# 3-PM25-STM32F103C8-170426.net
KiCad netlist of a schematic drawn in Altium Designer
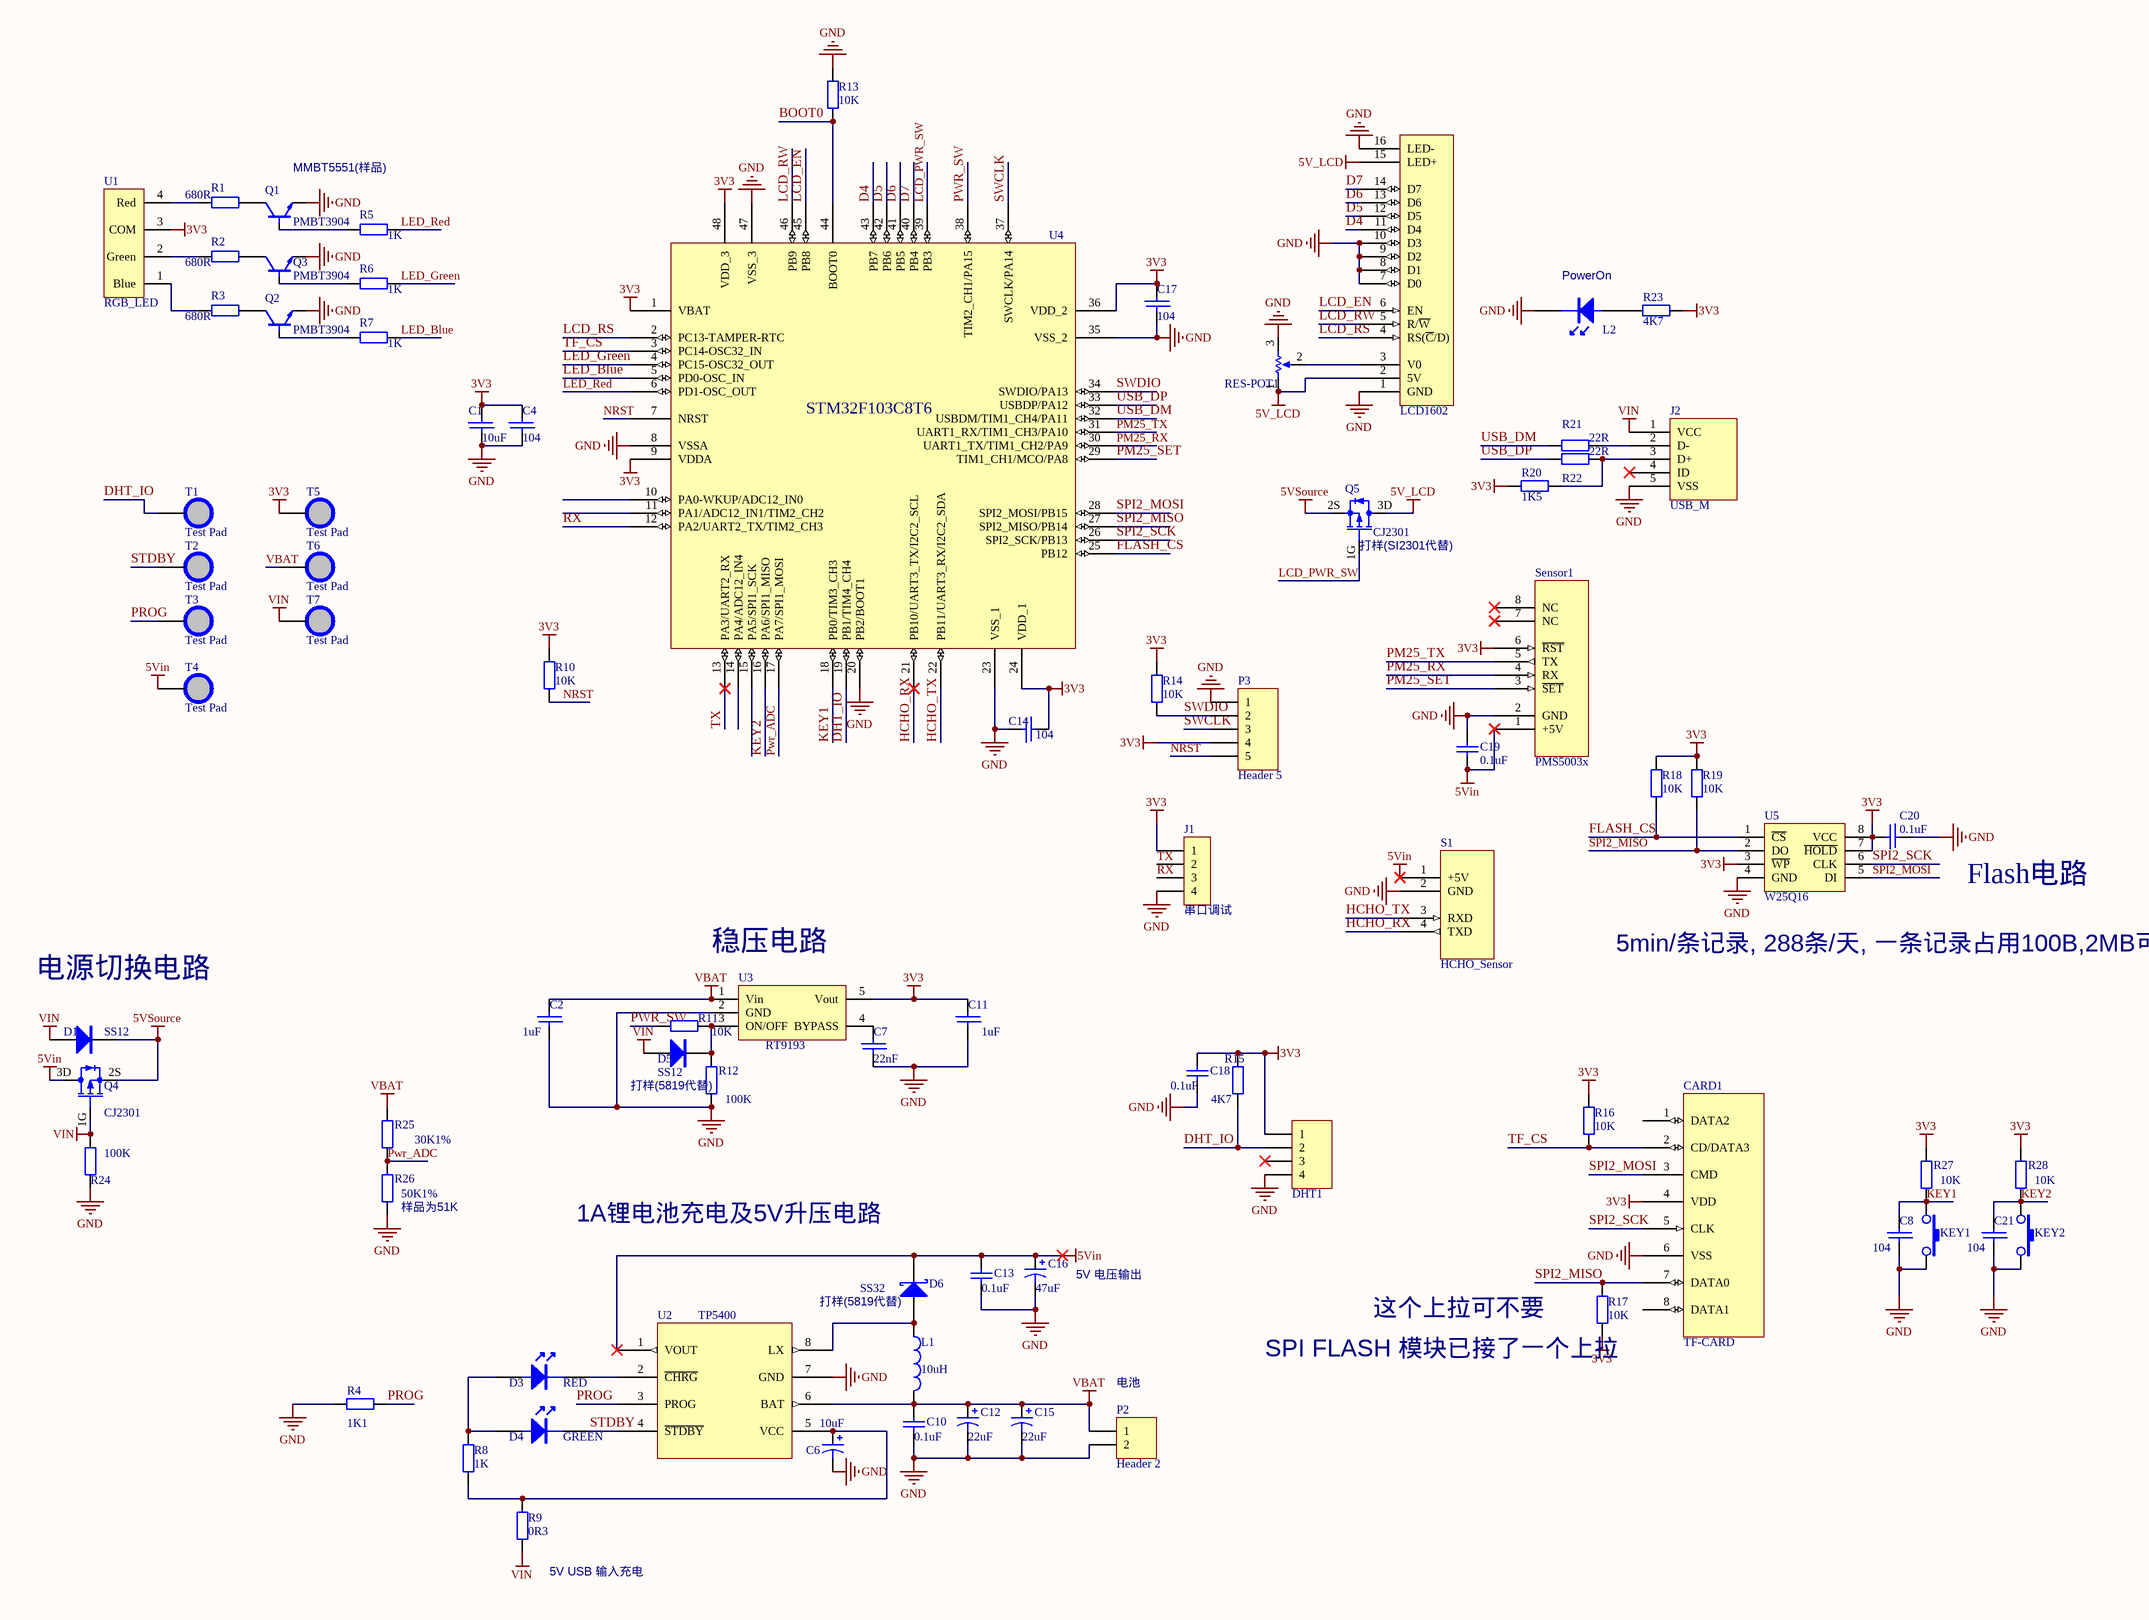
[diagram p0: 3-PM25-STM32F103C8-170426.SchDoc]

(export (version "E")
  (design (tool "Eeschema 10.0.6"))
  (components
    (comp (ref "C1")
      (value "10uF")
      (footprint "LC0805_Std")
      (fields (field (name "Comment") "10uF (106) ±10% 25V,0805"))
      (libsource (lib "元件总库") (part "普通电容"))
    )
    (comp (ref "C2")
      (value "1uF (105) ±10% 50V ,0603")
      (footprint "LC0603_Std")
      (fields (field (name "ALTIUM_UNNAMED_1") "1uF"))
      (libsource (lib "元件总库") (part "普通电容"))
    )
    (comp (ref "C4")
      (value "104")
      (footprint "LC0603_Std")
      (fields (field (name "Comment") "100nF(104) ±10% 50V,0603"))
      (libsource (lib "元件总库") (part "普通电容"))
    )
    (comp (ref "C6")
      (value "10uF")
      (footprint "LC0805_Std")
      (fields (field (name "Comment") "10uF (106) ±10% 25V,0805") (field (name "PUBLISHER") "Altium Limited"))
      (libsource (lib "Miscellaneous Devices") (part "Cap Pol1"))
    )
    (comp (ref "C7")
      (value "22nF (223) ±10% 50V,0603")
      (footprint "LC0603_Std")
      (fields (field (name "ALTIUM_UNNAMED_1") "22nF"))
      (libsource (lib "元件总库") (part "普通电容"))
    )
    (comp (ref "C8")
      (value "104")
      (footprint "LC0603_Std")
      (fields (field (name "Comment") "100nF (104) ±10% 50V,0603"))
      (libsource (lib "元件总库") (part "普通电容"))
    )
    (comp (ref "C10")
      (value "0.1uF")
      (footprint "LC0603_Std")
      (fields (field (name "Comment") "100nF(104) ±10% 50V,0603") (field (name "PUBLISHER") "Altium Limited"))
      (libsource (lib "Miscellaneous Devices") (part "Cap"))
    )
    (comp (ref "C11")
      (value "1uF (105) ±10% 50V ,0603")
      (footprint "LC0603_Std")
      (fields (field (name "ALTIUM_UNNAMED_1") "1uF"))
      (libsource (lib "元件总库") (part "普通电容"))
    )
    (comp (ref "C12")
      (value "22uF")
      (footprint "LC0805_Std")
      (fields (field (name "Comment") "22uF (226) ±20% 25V,0805") (field (name "PUBLISHER") "Altium Limited"))
      (libsource (lib "Miscellaneous Devices") (part "Cap Pol1"))
    )
    (comp (ref "C13")
      (value "0.1uF")
      (footprint "LC0603_Std")
      (fields (field (name "Comment") "100nF(104) ±10% 50V,0603") (field (name "PUBLISHER") "Altium Limited"))
      (libsource (lib "Miscellaneous Devices") (part "Cap"))
    )
    (comp (ref "C14")
      (value "104")
      (footprint "LC0603_Std")
      (fields (field (name "Comment") "100nF(104) ±10% 50V,0603"))
      (libsource (lib "元件总库") (part "普通电容"))
    )
    (comp (ref "C15")
      (value "22uF")
      (footprint "LC0805_Std")
      (fields (field (name "Comment") "22uF (226) ±20% 25V,0805") (field (name "PUBLISHER") "Altium Limited"))
      (libsource (lib "Miscellaneous Devices") (part "Cap Pol1"))
    )
    (comp (ref "C16")
      (value "47uF")
      (footprint "Cap-4x7")
      (fields (field (name "Comment") "47uF 16V,4*7,电解电容") (field (name "PUBLISHER") "Altium Limited"))
      (libsource (lib "Miscellaneous Devices") (part "Cap Pol1"))
    )
    (comp (ref "C17")
      (value "104")
      (footprint "LC0603_Std")
      (fields (field (name "Comment") "100nF(104) ±10% 50V,0603"))
      (libsource (lib "元件总库") (part "普通电容"))
    )
    (comp (ref "C18")
      (value "0.1uF")
      (footprint "LC0603_Std")
      (description "Capacitor")
      (fields (field (name "Comment") "100nF(104) ±10% 50V,0603") (field (name "PUBLISHER") "Altium Limited"))
      (libsource (lib "Miscellaneous Devices") (part "Cap"))
    )
    (comp (ref "C19")
      (value "0.1uF")
      (footprint "LC0603_Std")
      (description "Capacitor")
      (fields (field (name "Comment") "100nF(104) ±10% 50V,0603") (field (name "PUBLISHER") "Altium Limited"))
      (libsource (lib "Miscellaneous Devices") (part "Cap"))
    )
    (comp (ref "C20")
      (value "100nF(104) ±10% 50V,0603")
      (footprint "LC0603_Std")
      (fields (field (name "ALTIUM_UNNAMED_1") "0.1uF"))
      (libsource (lib "元件总库") (part "普通电容"))
    )
    (comp (ref "C21")
      (value "104")
      (footprint "LC0603_Std")
      (fields (field (name "Comment") "100nF (104) ±10% 50V,0603"))
      (libsource (lib "元件总库") (part "普通电容"))
    )
    (comp (ref "CARD1")
      (value "TF-CARD")
      (footprint "TF-CARD")
      (libsource (lib "My_SchLib_2014_04_01") (part "TF-CARD"))
    )
    (comp (ref "D1")
      (value "5819,SS12")
      (footprint "SOD-123-5819")
      (fields (field (name "ALTIUM_UNNAMED_1") "SS12"))
      (libsource (lib "元件总库") (part "二极管"))
    )
    (comp (ref "D3")
      (value "RED")
      (footprint "LC0603_Std")
      (fields (field (name "Comment") "红灯,发光二极, C2286,0603"))
      (libsource (lib "Miscellaneous Devices") (part "LED"))
    )
    (comp (ref "D4")
      (value "GREEN")
      (footprint "LC0603_Std")
      (fields (field (name "Comment") "绿灯,发光二极, C72043, 0603"))
      (libsource (lib "Miscellaneous Devices") (part "LED"))
    )
    (comp (ref "D5")
      (value "5819,SS12")
      (footprint "SOD-123-5819")
      (fields (field (name "ALTIUM_UNNAMED_1") "SS12"))
      (libsource (lib "元件总库") (part "二极管"))
    )
    (comp (ref "D6")
      (value "B5819W SL,SOD123,SS32,20V,3A,VF=0.55V@3A,DO-214AC")
      (footprint "SOD-123-5819")
      (fields (field (name "NAME") "SS32") (field (name "PUBLISHER") "Altium Limited"))
      (libsource (lib "Miscellaneous Devices") (part "D Schottky"))
    )
    (comp (ref "DHT1")
      (value "Header 4")
      (footprint "DHT11")
      (description "接插件")
      (fields (field (name "PUBLISHER") "Altium Limited"))
      (libsource (lib "fszhang") (part "Header 4"))
    )
    (comp (ref "J1") (value "串口调试") (footprint "HDR1X4") (libsource (lib "排针") (part "CON4")))
    (comp (ref "J2")
      (value "USB_M")
      (footprint "micro-USB-B")
      (description "MicroUSB接口")
      (libsource (lib "fszhang") (part "USB_M"))
    )
    (comp (ref "KEY1") (value "轻触开关") (footprint "轻触开关-6x6x6") (libsource (lib "元件总库") (part "轻触开关")))
    (comp (ref "KEY2") (value "轻触开关") (footprint "轻触开关-6x6x6") (libsource (lib "元件总库") (part "轻触开关")))
    (comp (ref "L1")
      (value "10uH")
      (footprint "LC0603_Std")
      (fields (field (name "Comment") "10uH ±10%,0603") (field (name "PUBLISHER") "Altium Limited"))
      (libsource (lib "Miscellaneous Devices") (part "Inductor"))
    )
    (comp (ref "L2")
      (value "单色蓝灯, 发光二极管,0603")
      (footprint "LC0603_Std")
      (libsource (lib "Miscellaneous Devices") (part "LED"))
    )
    (comp (ref "LCD1")
      (value "LCD1602")
      (footprint "LCD1602_KS0066")
      (libsource (lib "My_SchLib_2014_04_01") (part "LCD1602_KS0066"))
    )
    (comp (ref "P2")
      (value "Header 2")
      (footprint "XH-2A-2P")
      (description "Header, 2-Pin")
      (fields (field (name "PUBLISHER") "Altium Limited"))
      (libsource (lib "Miscellaneous Connectors") (part "Header 2"))
    )
    (comp (ref "P3")
      (value "Header 5")
      (footprint "HDR1X5")
      (description "Header, 5-Pin")
      (fields (field (name "PUBLISHER") "Altium Limited"))
      (libsource (lib "Miscellaneous Connectors") (part "Header 5"))
    )
    (comp (ref "Q1") (value "PMBT3904") (footprint "SOT23-NPN") (libsource (lib "元件总库") (part "NPN")))
    (comp (ref "Q2") (value "PMBT3904") (footprint "SOT23-NPN") (libsource (lib "元件总库") (part "NPN")))
    (comp (ref "Q3") (value "PMBT3904") (footprint "SOT23-NPN") (libsource (lib "元件总库") (part "NPN")))
    (comp (ref "Q4")
      (value "CJ2301")
      (footprint "SOT-23_SI2301")
      (libsource (lib "My_SchLib_2014_04_01") (part "PMOS"))
    )
    (comp (ref "Q5") (value "CJ2301") (footprint "SOT-23_SI2301") (libsource (lib "") (part "PMOS_1")))
    (comp (ref "R1")
      (value "680R")
      (footprint "LC0603_Std")
      (fields (field (name "Comment") "680Ω (6800) ±1%"))
      (libsource (lib "元件总库") (part "电阻"))
    )
    (comp (ref "R2")
      (value "680R")
      (footprint "LC0603_Std")
      (fields (field (name "Comment") "680Ω (6800) ±1%"))
      (libsource (lib "元件总库") (part "电阻"))
    )
    (comp (ref "R3")
      (value "680R")
      (footprint "LC0603_Std")
      (fields (field (name "Comment") "680Ω (6800) ±1%"))
      (libsource (lib "元件总库") (part "电阻"))
    )
    (comp (ref "R4")
      (value "1K1")
      (footprint "LC0603_Std")
      (description "Resistor")
      (fields (field (name "Comment") "1.1KΩ (1101) ±1%,0603") (field (name "PUBLISHER") "Altium Limited"))
      (libsource (lib "") (part "Res2_3"))
    )
    (comp (ref "R5")
      (value "1K")
      (footprint "LC0603_Std")
      (fields (field (name "Comment") "1KΩ (1001) ±1%,0603"))
      (libsource (lib "元件总库") (part "电阻"))
    )
    (comp (ref "R6")
      (value "1K")
      (footprint "LC0603_Std")
      (fields (field (name "Comment") "1KΩ (1001) ±1%,0603"))
      (libsource (lib "元件总库") (part "电阻"))
    )
    (comp (ref "R7")
      (value "1K")
      (footprint "LC0603_Std")
      (fields (field (name "Comment") "1KΩ (1001) ±1%,0603"))
      (libsource (lib "元件总库") (part "电阻"))
    )
    (comp (ref "R8")
      (value "1K")
      (footprint "LC0603_Std")
      (description "Resistor")
      (fields (field (name "Comment") "1KΩ (1001) ±1%,0603") (field (name "PUBLISHER") "Altium Limited"))
      (libsource (lib "") (part "Res2_2"))
    )
    (comp (ref "R9")
      (value "0R3")
      (footprint "LC0805_Std")
      (description "Resistor")
      (fields (field (name "Comment") "0.3Ω (R300) ±1%,0805") (field (name "PUBLISHER") "Altium Limited"))
      (libsource (lib "Miscellaneous Devices") (part "Res2"))
    )
    (comp (ref "R10")
      (value "10K")
      (footprint "LC0603_Std")
      (description "Risistor")
      (fields (field (name "Comment") "10KΩ (1002) ±1%,0603"))
      (libsource (lib "") (part "Res-C0805_1"))
    )
    (comp (ref "R11")
      (value "10KΩ (1002) ±1%,0603")
      (footprint "LC0603_Std")
      (fields (field (name "ALTIUM_UNNAMED_1") "10K"))
      (libsource (lib "元件总库") (part "电阻"))
    )
    (comp (ref "R12")
      (value "100KΩ (1003) ±1%,0603")
      (footprint "LC0603_Std")
      (fields (field (name "ALTIUM_UNNAMED_1") "100K"))
      (libsource (lib "元件总库") (part "电阻"))
    )
    (comp (ref "R13")
      (value "10K")
      (footprint "LC0603_Std")
      (description "Risistor")
      (fields (field (name "Comment") "10KΩ (1002) ±1%,0603"))
      (libsource (lib "") (part "Res-C0805_1"))
    )
    (comp (ref "R14")
      (value "10K")
      (footprint "LC0603_Std")
      (description "Risistor")
      (fields (field (name "Comment") "10KΩ (1002) ±1%,0603"))
      (libsource (lib "") (part "Res-C0805_2"))
    )
    (comp (ref "R15")
      (value "4K7")
      (footprint "LC0603_Std")
      (description "Resistor")
      (fields (field (name "Comment") "4.7KΩ (4701) ±1%,0603") (field (name "PUBLISHER") "Altium Limited"))
      (libsource (lib "Miscellaneous Devices") (part "Res2"))
    )
    (comp (ref "R16")
      (value "10K")
      (footprint "LC0603_Std")
      (description "Risistor")
      (fields (field (name "Comment") "10KΩ (1002) ±1%,0603"))
      (libsource (lib "") (part "Res-C0805_2"))
    )
    (comp (ref "R17")
      (value "10K")
      (footprint "LC0603_Std")
      (description "Risistor")
      (fields (field (name "Comment") "10KΩ (1002) ±1%,0603"))
      (libsource (lib "") (part "Res-C0805_2"))
    )
    (comp (ref "R18")
      (value "10K")
      (footprint "LC0603_Std")
      (description "Risistor")
      (fields (field (name "Comment") "10KΩ (1002) ±1%,0603"))
      (libsource (lib "") (part "Res-C0805_2"))
    )
    (comp (ref "R19")
      (value "10K")
      (footprint "LC0603_Std")
      (description "Risistor")
      (fields (field (name "Comment") "10KΩ (1002) ±1%,0603"))
      (libsource (lib "") (part "Res-C0805_2"))
    )
    (comp (ref "R20")
      (value "1K5")
      (footprint "LC0603_Std")
      (description "Risistor")
      (fields (field (name "Comment") "1.5KΩ (1501) ±1%,0603"))
      (libsource (lib "My_Integrated_Library") (part "Res-C0805"))
    )
    (comp (ref "R21")
      (value "22R")
      (footprint "LC0603_Std")
      (description "Risistor")
      (fields (field (name "Comment") "22Ω (22R0) ±1%,0603"))
      (libsource (lib "My_Integrated_Library") (part "Res-C0805"))
    )
    (comp (ref "R22")
      (value "22R")
      (footprint "LC0603_Std")
      (description "Risistor")
      (fields (field (name "Comment") "22Ω (22R0) ±1%,0603"))
      (libsource (lib "My_Integrated_Library") (part "Res-C0805"))
    )
    (comp (ref "R23")
      (value "4K7")
      (footprint "LC0603_Std")
      (description "Resistor")
      (fields (field (name "Comment") "4.7KΩ (4701) ±1%,0603") (field (name "PUBLISHER") "Altium Limited"))
      (libsource (lib "") (part "Res2_1"))
    )
    (comp (ref "R24")
      (value "100KΩ (1003) ±1%,0603")
      (footprint "LC0603_Std")
      (fields (field (name "ALTIUM_UNNAMED_1") "100K"))
      (libsource (lib "元件总库") (part "电阻"))
    )
    (comp (ref "R25")
      (value "30KΩ (3002) ±1% ,0603")
      (footprint "LC0603_Std")
      (fields (field (name "ALTIUM_UNNAMED_1") "30K1%"))
      (libsource (lib "元件总库") (part "电阻"))
    )
    (comp (ref "R26")
      (value "51KΩ (5102) ±1%")
      (footprint "LC0603_Std")
      (fields (field (name "ALTIUM_UNNAMED_1") "50K1%"))
      (libsource (lib "元件总库") (part "电阻"))
    )
    (comp (ref "R27")
      (value "10K")
      (footprint "LC0603_Std")
      (fields (field (name "Comment") "10KΩ (1002) ±1%,0603"))
      (libsource (lib "") (part "电阻_1"))
    )
    (comp (ref "R28")
      (value "10K")
      (footprint "LC0603_Std")
      (fields (field (name "Comment") "10KΩ (1002) ±1%,0603"))
      (libsource (lib "") (part "电阻_1"))
    )
    (comp (ref "RES-POT1")
      (value "RES-POT-RM0065-V1")
      (footprint "RES-POT-RM0065-V1")
      (libsource (lib "My_SchLib_2014_04_01") (part "RES-POT-RM0065-V1"))
    )
    (comp (ref "S1")
      (value "HCHO_Sensor")
      (footprint "HCHO_Header")
      (libsource (lib "My_SchLib_2014_04_01") (part "HCHO_Sensor"))
    )
    (comp (ref "Sensor1")
      (value "PMS5003x")
      (footprint "PM25_Header")
      (libsource (lib "My_SchLib_2014_04_01") (part "PMS5003x_Sensor"))
    )
    (comp (ref "T1") (value "Test Pad") (footprint "TestPoint") (libsource (lib "元件总库") (part "Test Pad")))
    (comp (ref "T2") (value "Test Pad") (footprint "TestPoint") (libsource (lib "元件总库") (part "Test Pad")))
    (comp (ref "T3") (value "Test Pad") (footprint "TestPoint") (libsource (lib "元件总库") (part "Test Pad")))
    (comp (ref "T4") (value "Test Pad") (footprint "TestPoint") (libsource (lib "元件总库") (part "Test Pad")))
    (comp (ref "T5") (value "Test Pad") (footprint "TestPoint") (libsource (lib "元件总库") (part "Test Pad")))
    (comp (ref "T6") (value "Test Pad") (footprint "TestPoint") (libsource (lib "元件总库") (part "Test Pad")))
    (comp (ref "T7") (value "Test Pad") (footprint "TestPoint") (libsource (lib "元件总库") (part "Test Pad")))
    (comp (ref "U1") (value "RGB_LED") (footprint "LED_RGB") (libsource (lib "元件总库") (part "RGB_LED")))
    (comp (ref "U2")
      (value "TP5400")
      (footprint "TP5400-SOP-8")
      (description "SOIC-8_EP_150mil")
      (libsource (lib "My_SchLib_2014_04_01") (part "TP5400"))
    )
    (comp (ref "U3") (value "RT9193") (footprint "SOT-23-5_RT9193") (libsource (lib "元件总库") (part "LP2985")))
    (comp (ref "U4")
      (value "STM32F103C8T6")
      (footprint "STM32F103C8T6-LQFP-48")
      (fields (field (name "Comment") "STM32F103C8T6,LQFP-48"))
      (libsource (lib "My_SchLib_2014_04_01") (part "STM32F103C8T6_LQFP48"))
    )
    (comp (ref "U5")
      (value "W25Q16")
      (footprint "SOIC-8_W25Q16JVSS")
      (libsource (lib "元件总库") (part "W25Q16"))
    )
  )
  (nets
    (net (code "1") (name "/BOOT0") (class "Default")
      (node (ref "R13") (pin "1") (pinfunction "1_1") (pintype "passive"))
      (node (ref "U4") (pin "44") (pinfunction "BOOT0_44") (pintype "passive"))
    )
    (net (code "2") (name "/D4") (class "Default")
      (node (ref "LCD1") (pin "11") (pinfunction "D4_11") (pintype "bidirectional"))
      (node (ref "U4") (pin "43") (pinfunction "PB7_43") (pintype "bidirectional"))
    )
    (net (code "3") (name "/D5") (class "Default")
      (node (ref "LCD1") (pin "12") (pinfunction "D5_12") (pintype "bidirectional"))
      (node (ref "U4") (pin "42") (pinfunction "PB6_42") (pintype "bidirectional"))
    )
    (net (code "4") (name "/D6") (class "Default")
      (node (ref "LCD1") (pin "13") (pinfunction "D6_13") (pintype "bidirectional"))
      (node (ref "U4") (pin "41") (pinfunction "PB5_41") (pintype "bidirectional"))
    )
    (net (code "5") (name "/D7") (class "Default")
      (node (ref "LCD1") (pin "14") (pinfunction "D7_14") (pintype "bidirectional"))
      (node (ref "U4") (pin "40") (pinfunction "PB4_40") (pintype "bidirectional"))
    )
    (net (code "6") (name "/DHT_IO") (class "Default")
      (node (ref "DHT1") (pin "2") (pinfunction "2_2") (pintype "passive"))
      (node (ref "R15") (pin "1") (pinfunction "1_1") (pintype "passive"))
      (node (ref "T1") (pin "1") (pinfunction "1_1") (pintype "passive"))
      (node (ref "U4") (pin "19") (pinfunction "PB1/TIM4_CH4_19") (pintype "bidirectional"))
    )
    (net (code "7") (name "/FLASH_CS") (class "Default")
      (node (ref "R18") (pin "2") (pinfunction "2_2") (pintype "passive"))
      (node (ref "U4") (pin "25") (pinfunction "PB12_25") (pintype "bidirectional"))
      (node (ref "U5") (pin "1") (pinfunction "~{CS}_1") (pintype "passive"))
    )
    (net (code "8") (name "/HCHO_RX") (class "Default")
      (node (ref "S1") (pin "4") (pinfunction "TXD_4") (pintype "output"))
      (node (ref "U4") (pin "21") (pinfunction "PB10/UART3_TX/I2C2_SCL_21") (pintype "bidirectional"))
    )
    (net (code "9") (name "/HCHO_TX") (class "Default")
      (node (ref "S1") (pin "3") (pinfunction "RXD_3") (pintype "input"))
      (node (ref "U4") (pin "22") (pinfunction "PB11/UART3_RX/I2C2_SDA_22") (pintype "bidirectional"))
    )
    (net (code "10") (name "/KEY1") (class "Default")
      (node (ref "C8") (pin "1") (pinfunction "1_1") (pintype "passive"))
      (node (ref "KEY1") (pin "1") (pinfunction "1_1") (pintype "passive"))
      (node (ref "R27") (pin "1") (pinfunction "1_1") (pintype "passive"))
      (node (ref "U4") (pin "18") (pinfunction "PB0/TIM3_CH3_18") (pintype "bidirectional"))
    )
    (net (code "11") (name "/KEY2") (class "Default")
      (node (ref "C21") (pin "1") (pinfunction "1_1") (pintype "passive"))
      (node (ref "KEY2") (pin "1") (pinfunction "1_1") (pintype "passive"))
      (node (ref "R28") (pin "1") (pinfunction "1_1") (pintype "passive"))
      (node (ref "U4") (pin "16") (pinfunction "PA6/SPI1_MISO_16") (pintype "bidirectional"))
    )
    (net (code "12") (name "/LCD_EN") (class "Default")
      (node (ref "LCD1") (pin "6") (pinfunction "EN_6") (pintype "input"))
      (node (ref "U4") (pin "45") (pinfunction "PB8_45") (pintype "bidirectional"))
    )
    (net (code "13") (name "/LCD_PWR_SW") (class "Default")
      (node (ref "Q5") (pin "1G") (pinfunction "G_1G") (pintype "passive"))
      (node (ref "U4") (pin "39") (pinfunction "PB3_39") (pintype "bidirectional"))
    )
    (net (code "14") (name "/LCD_RS") (class "Default")
      (node (ref "LCD1") (pin "4") (pinfunction "RS(~{C}/D)_4") (pintype "input"))
      (node (ref "U4") (pin "2") (pinfunction "PC13-TAMPER-RTC_2") (pintype "bidirectional"))
    )
    (net (code "15") (name "/LCD_RW") (class "Default")
      (node (ref "LCD1") (pin "5") (pinfunction "R/~{W}_5") (pintype "input"))
      (node (ref "U4") (pin "46") (pinfunction "PB9_46") (pintype "bidirectional"))
    )
    (net (code "16") (name "/LED_Blue") (class "Default")
      (node (ref "R7") (pin "2") (pinfunction "2_2") (pintype "passive"))
      (node (ref "U4") (pin "5") (pinfunction "PD0-OSC_IN_5") (pintype "bidirectional"))
    )
    (net (code "17") (name "/LED_Green") (class "Default")
      (node (ref "R6") (pin "1") (pinfunction "1_1") (pintype "passive"))
      (node (ref "U4") (pin "4") (pinfunction "PC15-OSC32_OUT_4") (pintype "bidirectional"))
    )
    (net (code "18") (name "/LED_Red") (class "Default")
      (node (ref "R5") (pin "1") (pinfunction "1_1") (pintype "passive"))
      (node (ref "U4") (pin "6") (pinfunction "PD1-OSC_OUT_6") (pintype "bidirectional"))
    )
    (net (code "19") (name "/NRST") (class "Default")
      (node (ref "P3") (pin "5") (pinfunction "5_5") (pintype "passive"))
      (node (ref "R10") (pin "1") (pinfunction "1_1") (pintype "passive"))
      (node (ref "U4") (pin "7") (pinfunction "NRST_7") (pintype "passive"))
    )
    (net (code "20") (name "/PM25_RX") (class "Default")
      (node (ref "Sensor1") (pin "4") (pinfunction "RX_4") (pintype "input"))
      (node (ref "U4") (pin "30") (pinfunction "UART1_TX/TIM1_CH2/PA9_30") (pintype "bidirectional"))
    )
    (net (code "21") (name "/PM25_SET") (class "Default")
      (node (ref "Sensor1") (pin "3") (pinfunction "~{SET}_3") (pintype "input"))
      (node (ref "U4") (pin "29") (pinfunction "TIM1_CH1/MCO/PA8_29") (pintype "bidirectional"))
    )
    (net (code "22") (name "/PM25_TX") (class "Default")
      (node (ref "Sensor1") (pin "5") (pinfunction "TX_5") (pintype "output"))
      (node (ref "U4") (pin "31") (pinfunction "UART1_RX/TIM1_CH3/PA10_31") (pintype "bidirectional"))
    )
    (net (code "23") (name "/PROG") (class "Default")
      (node (ref "R4") (pin "2") (pinfunction "2_2") (pintype "passive"))
      (node (ref "T3") (pin "1") (pinfunction "1_1") (pintype "passive"))
      (node (ref "U2") (pin "3") (pinfunction "PROG_3") (pintype "passive"))
    )
    (net (code "24") (name "/PWR_SW") (class "Default")
      (node (ref "R11") (pin "1") (pinfunction "1_1") (pintype "passive"))
      (node (ref "U4") (pin "38") (pinfunction "TIM2_CH1/PA15_38") (pintype "bidirectional"))
    )
    (net (code "25") (name "/Pwr_ADC") (class "Default")
      (node (ref "R25") (pin "2") (pinfunction "2_2") (pintype "passive"))
      (node (ref "R26") (pin "1") (pinfunction "1_1") (pintype "passive"))
      (node (ref "U4") (pin "17") (pinfunction "PA7/SPI1_MOSI_17") (pintype "bidirectional"))
    )
    (net (code "26") (name "/RX") (class "Default")
      (node (ref "J1") (pin "3") (pinfunction "3_3") (pintype "passive"))
      (node (ref "U4") (pin "12") (pinfunction "PA2/UART2_TX/TIM2_CH3_12") (pintype "bidirectional"))
    )
    (net (code "27") (name "/SPI2_MISO") (class "Default")
      (node (ref "CARD1") (pin "7") (pinfunction "DATA0_7") (pintype "bidirectional"))
      (node (ref "R17") (pin "1") (pinfunction "1_1") (pintype "passive"))
      (node (ref "R19") (pin "2") (pinfunction "2_2") (pintype "passive"))
      (node (ref "U4") (pin "27") (pinfunction "SPI2_MISO/PB14_27") (pintype "bidirectional"))
      (node (ref "U5") (pin "2") (pinfunction "DO_2") (pintype "passive"))
    )
    (net (code "28") (name "/SPI2_MOSI") (class "Default")
      (node (ref "CARD1") (pin "3") (pinfunction "CMD_3") (pintype "passive"))
      (node (ref "U4") (pin "28") (pinfunction "SPI2_MOSI/PB15_28") (pintype "bidirectional"))
      (node (ref "U5") (pin "5") (pinfunction "DI_5") (pintype "passive"))
    )
    (net (code "29") (name "/SPI2_SCK") (class "Default")
      (node (ref "CARD1") (pin "5") (pinfunction "CLK_5") (pintype "input"))
      (node (ref "U4") (pin "26") (pinfunction "SPI2_SCK/PB13_26") (pintype "bidirectional"))
      (node (ref "U5") (pin "6") (pinfunction "CLK_6") (pintype "passive"))
    )
    (net (code "30") (name "/STDBY") (class "Default")
      (node (ref "D4") (pin "K") (pinfunction "2_K") (pintype "passive"))
      (node (ref "T2") (pin "1") (pinfunction "1_1") (pintype "passive"))
      (node (ref "U2") (pin "4") (pinfunction "~{STDBY}_4") (pintype "passive"))
    )
    (net (code "31") (name "/SWCLK") (class "Default")
      (node (ref "P3") (pin "3") (pinfunction "3_3") (pintype "passive"))
      (node (ref "U4") (pin "37") (pinfunction "SWCLK/PA14_37") (pintype "bidirectional"))
    )
    (net (code "32") (name "/SWDIO") (class "Default")
      (node (ref "P3") (pin "2") (pinfunction "2_2") (pintype "passive"))
      (node (ref "R14") (pin "2") (pinfunction "2_2") (pintype "passive"))
      (node (ref "U4") (pin "34") (pinfunction "SWDIO/PA13_34") (pintype "bidirectional"))
    )
    (net (code "33") (name "/TF_CS") (class "Default")
      (node (ref "CARD1") (pin "2") (pinfunction "CD/DATA3_2") (pintype "bidirectional"))
      (node (ref "R16") (pin "2") (pinfunction "2_2") (pintype "passive"))
      (node (ref "U4") (pin "3") (pinfunction "PC14-OSC32_IN_3") (pintype "bidirectional"))
    )
    (net (code "34") (name "/TX") (class "Default")
      (node (ref "J1") (pin "2") (pinfunction "2_2") (pintype "passive"))
      (node (ref "U4") (pin "13") (pinfunction "PA3/UART2_RX_13") (pintype "bidirectional"))
    )
    (net (code "35") (name "/USB_DM") (class "Default")
      (node (ref "R21") (pin "1") (pinfunction "1_1") (pintype "passive"))
      (node (ref "U4") (pin "32") (pinfunction "USBDM/TIM1_CH4/PA11_32") (pintype "bidirectional"))
    )
    (net (code "36") (name "/USB_DP") (class "Default")
      (node (ref "R22") (pin "1") (pinfunction "1_1") (pintype "passive"))
      (node (ref "U4") (pin "33") (pinfunction "USBDP/PA12_33") (pintype "bidirectional"))
    )
    (net (code "37") (name "3V3") (class "Default")
      (node (ref "C1") (pin "2") (pinfunction "2_2") (pintype "passive"))
      (node (ref "C11") (pin "1") (pinfunction "1_1") (pintype "passive"))
      (node (ref "C14") (pin "1") (pinfunction "1_1") (pintype "passive"))
      (node (ref "C17") (pin "1") (pinfunction "1_1") (pintype "passive"))
      (node (ref "C18") (pin "1") (pinfunction "1_1") (pintype "passive"))
      (node (ref "C20") (pin "1") (pinfunction "1_1") (pintype "passive"))
      (node (ref "C4") (pin "2") (pinfunction "2_2") (pintype "passive"))
      (node (ref "CARD1") (pin "4") (pinfunction "VDD_4") (pintype "power_in"))
      (node (ref "DHT1") (pin "1") (pinfunction "1_1") (pintype "passive"))
      (node (ref "J1") (pin "1") (pinfunction "1_1") (pintype "passive"))
      (node (ref "P3") (pin "4") (pinfunction "4_4") (pintype "passive"))
      (node (ref "R10") (pin "2") (pinfunction "2_2") (pintype "passive"))
      (node (ref "R14") (pin "1") (pinfunction "1_1") (pintype "passive"))
      (node (ref "R15") (pin "2") (pinfunction "2_2") (pintype "passive"))
      (node (ref "R16") (pin "1") (pinfunction "1_1") (pintype "passive"))
      (node (ref "R17") (pin "2") (pinfunction "2_2") (pintype "passive"))
      (node (ref "R18") (pin "1") (pinfunction "1_1") (pintype "passive"))
      (node (ref "R19") (pin "1") (pinfunction "1_1") (pintype "passive"))
      (node (ref "R20") (pin "1") (pinfunction "1_1") (pintype "passive"))
      (node (ref "R23") (pin "1") (pinfunction "1_1") (pintype "passive"))
      (node (ref "R27") (pin "2") (pinfunction "2_2") (pintype "passive"))
      (node (ref "R28") (pin "2") (pinfunction "2_2") (pintype "passive"))
      (node (ref "Sensor1") (pin "6") (pinfunction "~{RST}_6") (pintype "input"))
      (node (ref "T5") (pin "1") (pinfunction "1_1") (pintype "passive"))
      (node (ref "U1") (pin "3") (pinfunction "COM_3") (pintype "passive"))
      (node (ref "U3") (pin "5") (pinfunction "Vout_5") (pintype "passive"))
      (node (ref "U4") (pin "1") (pinfunction "VBAT_1") (pintype "power_in"))
      (node (ref "U4") (pin "24") (pinfunction "VDD_1_24") (pintype "power_in"))
      (node (ref "U4") (pin "36") (pinfunction "VDD_2_36") (pintype "power_in"))
      (node (ref "U4") (pin "48") (pinfunction "VDD_3_48") (pintype "power_in"))
      (node (ref "U4") (pin "9") (pinfunction "VDDA_9") (pintype "power_in"))
      (node (ref "U5") (pin "3") (pinfunction "~{WP}_3") (pintype "passive"))
      (node (ref "U5") (pin "7") (pinfunction "~{HOLD}_7") (pintype "passive"))
      (node (ref "U5") (pin "8") (pinfunction "VCC_8") (pintype "passive"))
    )
    (net (code "38") (name "5VSource") (class "Default")
      (node (ref "D1") (pin "K") (pinfunction "K_K") (pintype "passive"))
      (node (ref "Q4") (pin "2S") (pinfunction "S_2S") (pintype "passive"))
      (node (ref "Q5") (pin "2S") (pinfunction "S_2S") (pintype "passive"))
    )
    (net (code "39") (name "5V_LCD") (class "Default")
      (node (ref "LCD1") (pin "15") (pinfunction "LED+_15") (pintype "power_in"))
      (node (ref "LCD1") (pin "2") (pinfunction "5V_2") (pintype "power_in"))
      (node (ref "Q5") (pin "3D") (pinfunction "D_3D") (pintype "passive"))
      (node (ref "RES-POT1") (pin "1") (pinfunction "TOP_1") (pintype "passive"))
    )
    (net (code "40") (name "5Vin") (class "Default")
      (node (ref "C13") (pin "2") (pinfunction "2_2") (pintype "passive"))
      (node (ref "C16") (pin "1") (pinfunction "1_1") (pintype "passive"))
      (node (ref "C19") (pin "2") (pinfunction "2_2") (pintype "passive"))
      (node (ref "D6") (pin "2") (pinfunction "K_2") (pintype "passive"))
      (node (ref "Q4") (pin "3D") (pinfunction "D_3D") (pintype "passive"))
      (node (ref "S1") (pin "1") (pinfunction "+5V_1") (pintype "power_in"))
      (node (ref "Sensor1") (pin "1") (pinfunction "+5V_1") (pintype "power_in"))
      (node (ref "T4") (pin "1") (pinfunction "1_1") (pintype "passive"))
      (node (ref "U2") (pin "1") (pinfunction "VOUT_1") (pintype "output"))
    )
    (net (code "41") (name "GND") (class "Default")
      (node (ref "C1") (pin "1") (pinfunction "1_1") (pintype "passive"))
      (node (ref "C10") (pin "1") (pinfunction "1_1") (pintype "passive"))
      (node (ref "C11") (pin "2") (pinfunction "2_2") (pintype "passive"))
      (node (ref "C12") (pin "2") (pinfunction "2_2") (pintype "passive"))
      (node (ref "C13") (pin "1") (pinfunction "1_1") (pintype "passive"))
      (node (ref "C14") (pin "2") (pinfunction "2_2") (pintype "passive"))
      (node (ref "C15") (pin "2") (pinfunction "2_2") (pintype "passive"))
      (node (ref "C16") (pin "2") (pinfunction "2_2") (pintype "passive"))
      (node (ref "C17") (pin "2") (pinfunction "2_2") (pintype "passive"))
      (node (ref "C18") (pin "2") (pinfunction "2_2") (pintype "passive"))
      (node (ref "C19") (pin "1") (pinfunction "1_1") (pintype "passive"))
      (node (ref "C2") (pin "2") (pinfunction "2_2") (pintype "passive"))
      (node (ref "C20") (pin "2") (pinfunction "2_2") (pintype "passive"))
      (node (ref "C21") (pin "2") (pinfunction "2_2") (pintype "passive"))
      (node (ref "C4") (pin "1") (pinfunction "1_1") (pintype "passive"))
      (node (ref "C6") (pin "2") (pinfunction "2_2") (pintype "passive"))
      (node (ref "C7") (pin "2") (pinfunction "2_2") (pintype "passive"))
      (node (ref "C8") (pin "2") (pinfunction "2_2") (pintype "passive"))
      (node (ref "CARD1") (pin "6") (pinfunction "VSS_6") (pintype "power_in"))
      (node (ref "DHT1") (pin "4") (pinfunction "4_4") (pintype "passive"))
      (node (ref "J1") (pin "4") (pinfunction "4_4") (pintype "passive"))
      (node (ref "J2") (pin "5") (pinfunction "VSS_5") (pintype "passive"))
      (node (ref "KEY1") (pin "2") (pinfunction "2_2") (pintype "passive"))
      (node (ref "KEY2") (pin "2") (pinfunction "2_2") (pintype "passive"))
      (node (ref "L2") (pin "K") (pinfunction "2_K") (pintype "passive"))
      (node (ref "LCD1") (pin "1") (pinfunction "GND_1") (pintype "power_in"))
      (node (ref "LCD1") (pin "10") (pinfunction "D3_10") (pintype "bidirectional"))
      (node (ref "LCD1") (pin "16") (pinfunction "LED-_16") (pintype "power_in"))
      (node (ref "LCD1") (pin "7") (pinfunction "D0_7") (pintype "bidirectional"))
      (node (ref "LCD1") (pin "8") (pinfunction "D1_8") (pintype "bidirectional"))
      (node (ref "LCD1") (pin "9") (pinfunction "D2_9") (pintype "bidirectional"))
      (node (ref "P2") (pin "2") (pinfunction "2_2") (pintype "passive"))
      (node (ref "P3") (pin "1") (pinfunction "1_1") (pintype "passive"))
      (node (ref "Q1") (pin "2") (pinfunction "e_2") (pintype "passive"))
      (node (ref "Q2") (pin "2") (pinfunction "e_2") (pintype "passive"))
      (node (ref "Q3") (pin "2") (pinfunction "e_2") (pintype "passive"))
      (node (ref "R12") (pin "2") (pinfunction "2_2") (pintype "passive"))
      (node (ref "R13") (pin "2") (pinfunction "2_2") (pintype "passive"))
      (node (ref "R24") (pin "2") (pinfunction "2_2") (pintype "passive"))
      (node (ref "R26") (pin "2") (pinfunction "2_2") (pintype "passive"))
      (node (ref "R4") (pin "1") (pinfunction "1_1") (pintype "passive"))
      (node (ref "RES-POT1") (pin "3") (pinfunction "BOT_3") (pintype "passive"))
      (node (ref "S1") (pin "2") (pinfunction "GND_2") (pintype "power_in"))
      (node (ref "Sensor1") (pin "2") (pinfunction "GND_2") (pintype "power_in"))
      (node (ref "U2") (pin "7") (pinfunction "GND_7") (pintype "power_in"))
      (node (ref "U3") (pin "2") (pinfunction "GND_2") (pintype "passive"))
      (node (ref "U4") (pin "20") (pinfunction "PB2/BOOT1_20") (pintype "bidirectional"))
      (node (ref "U4") (pin "23") (pinfunction "VSS_1_23") (pintype "power_in"))
      (node (ref "U4") (pin "35") (pinfunction "VSS_2_35") (pintype "power_in"))
      (node (ref "U4") (pin "47") (pinfunction "VSS_3_47") (pintype "power_in"))
      (node (ref "U4") (pin "8") (pinfunction "VSSA_8") (pintype "power_in"))
      (node (ref "U5") (pin "4") (pinfunction "GND_4") (pintype "passive"))
    )
    (net (code "42") (name "Net-(D3-1)") (class "Default")
      (node (ref "D3") (pin "A") (pinfunction "1_A") (pintype "passive"))
      (node (ref "D4") (pin "A") (pinfunction "1_A") (pintype "passive"))
      (node (ref "R8") (pin "1") (pinfunction "1_1") (pintype "passive"))
    )
    (net (code "43") (name "Net-(D3-2)") (class "Default")
      (node (ref "D3") (pin "K") (pinfunction "2_K") (pintype "passive"))
      (node (ref "U2") (pin "2") (pinfunction "~{CHRG}_2") (pintype "passive"))
    )
    (net (code "44") (name "Net-(D6-A)") (class "Default")
      (node (ref "D6") (pin "1") (pinfunction "A_1") (pintype "passive"))
      (node (ref "L1") (pin "1") (pinfunction "1_1") (pintype "passive"))
      (node (ref "U2") (pin "8") (pinfunction "LX_8") (pintype "output"))
    )
    (net (code "45") (name "Net-(J2-D+)") (class "Default")
      (node (ref "J2") (pin "3") (pinfunction "D+_3") (pintype "passive"))
      (node (ref "R20") (pin "2") (pinfunction "2_2") (pintype "passive"))
      (node (ref "R22") (pin "2") (pinfunction "2_2") (pintype "passive"))
    )
    (net (code "46") (name "Net-(J2-D-)") (class "Default")
      (node (ref "J2") (pin "2") (pinfunction "D-_2") (pintype "passive"))
      (node (ref "R21") (pin "2") (pinfunction "2_2") (pintype "passive"))
    )
    (net (code "47") (name "Net-(L2-1)") (class "Default")
      (node (ref "L2") (pin "A") (pinfunction "1_A") (pintype "passive"))
      (node (ref "R23") (pin "2") (pinfunction "2_2") (pintype "passive"))
    )
    (net (code "48") (name "Net-(LCD1-V0)") (class "Default")
      (node (ref "LCD1") (pin "3") (pinfunction "V0_3") (pintype "power_in"))
      (node (ref "RES-POT1") (pin "2") (pinfunction "TAP_2") (pintype "passive"))
    )
    (net (code "49") (name "Net-(Q1-b)") (class "Default")
      (node (ref "Q1") (pin "1") (pinfunction "b_1") (pintype "passive"))
      (node (ref "R5") (pin "2") (pinfunction "2_2") (pintype "passive"))
    )
    (net (code "50") (name "Net-(Q1-c)") (class "Default")
      (node (ref "Q1") (pin "3") (pinfunction "c_3") (pintype "passive"))
      (node (ref "R1") (pin "1") (pinfunction "1_1") (pintype "passive"))
    )
    (net (code "51") (name "Net-(Q2-b)") (class "Default")
      (node (ref "Q2") (pin "1") (pinfunction "b_1") (pintype "passive"))
      (node (ref "R7") (pin "1") (pinfunction "1_1") (pintype "passive"))
    )
    (net (code "52") (name "Net-(Q2-c)") (class "Default")
      (node (ref "Q2") (pin "3") (pinfunction "c_3") (pintype "passive"))
      (node (ref "R3") (pin "1") (pinfunction "1_1") (pintype "passive"))
    )
    (net (code "53") (name "Net-(Q3-b)") (class "Default")
      (node (ref "Q3") (pin "1") (pinfunction "b_1") (pintype "passive"))
      (node (ref "R6") (pin "2") (pinfunction "2_2") (pintype "passive"))
    )
    (net (code "54") (name "Net-(Q3-c)") (class "Default")
      (node (ref "Q3") (pin "3") (pinfunction "c_3") (pintype "passive"))
      (node (ref "R2") (pin "1") (pinfunction "1_1") (pintype "passive"))
    )
    (net (code "55") (name "Net-(U1-Blue)") (class "Default")
      (node (ref "R3") (pin "2") (pinfunction "2_2") (pintype "passive"))
      (node (ref "U1") (pin "1") (pinfunction "Blue_1") (pintype "passive"))
    )
    (net (code "56") (name "Net-(U1-Green)") (class "Default")
      (node (ref "R2") (pin "2") (pinfunction "2_2") (pintype "passive"))
      (node (ref "U1") (pin "2") (pinfunction "Green_2") (pintype "passive"))
    )
    (net (code "57") (name "Net-(U1-Red)") (class "Default")
      (node (ref "R1") (pin "2") (pinfunction "2_2") (pintype "passive"))
      (node (ref "U1") (pin "4") (pinfunction "Red_4") (pintype "passive"))
    )
    (net (code "58") (name "Net-(U2-VCC)") (class "Default")
      (node (ref "C6") (pin "1") (pinfunction "1_1") (pintype "passive"))
      (node (ref "R8") (pin "2") (pinfunction "2_2") (pintype "passive"))
      (node (ref "R9") (pin "2") (pinfunction "2_2") (pintype "passive"))
      (node (ref "U2") (pin "5") (pinfunction "VCC_5") (pintype "power_in"))
    )
    (net (code "59") (name "Net-(U3-BYPASS)") (class "Default")
      (node (ref "C7") (pin "1") (pinfunction "1_1") (pintype "passive"))
      (node (ref "U3") (pin "4") (pinfunction "BYPASS_4") (pintype "passive"))
    )
    (net (code "60") (name "Net-(U3-ON{slash}OFF)") (class "Default")
      (node (ref "D5") (pin "K") (pinfunction "K_K") (pintype "passive"))
      (node (ref "R11") (pin "2") (pinfunction "2_2") (pintype "passive"))
      (node (ref "R12") (pin "1") (pinfunction "1_1") (pintype "passive"))
      (node (ref "U3") (pin "3") (pinfunction "ON/OFF_3") (pintype "passive"))
    )
    (net (code "61") (name "VBAT") (class "Default")
      (node (ref "C10") (pin "2") (pinfunction "2_2") (pintype "passive"))
      (node (ref "C12") (pin "1") (pinfunction "1_1") (pintype "passive"))
      (node (ref "C15") (pin "1") (pinfunction "1_1") (pintype "passive"))
      (node (ref "C2") (pin "1") (pinfunction "1_1") (pintype "passive"))
      (node (ref "L1") (pin "2") (pinfunction "2_2") (pintype "passive"))
      (node (ref "P2") (pin "1") (pinfunction "1_1") (pintype "passive"))
      (node (ref "R25") (pin "1") (pinfunction "1_1") (pintype "passive"))
      (node (ref "T6") (pin "1") (pinfunction "1_1") (pintype "passive"))
      (node (ref "U2") (pin "6") (pinfunction "BAT_6") (pintype "output"))
      (node (ref "U3") (pin "1") (pinfunction "Vin_1") (pintype "passive"))
    )
    (net (code "62") (name "VIN") (class "Default")
      (node (ref "D1") (pin "A") (pinfunction "A_A") (pintype "passive"))
      (node (ref "D5") (pin "A") (pinfunction "A_A") (pintype "passive"))
      (node (ref "J2") (pin "1") (pinfunction "VCC_1") (pintype "passive"))
      (node (ref "Q4") (pin "1G") (pinfunction "G_1G") (pintype "passive"))
      (node (ref "R24") (pin "1") (pinfunction "1_1") (pintype "passive"))
      (node (ref "R9") (pin "1") (pinfunction "1_1") (pintype "passive"))
      (node (ref "T7") (pin "1") (pinfunction "1_1") (pintype "passive"))
    )
    (net (code "63") (name "unconnected-(CARD1-DATA1-Pad8)") (class "Default")
      (node (ref "CARD1") (pin "8") (pinfunction "DATA1_8") (pintype "bidirectional"))
    )
    (net (code "64") (name "unconnected-(CARD1-DATA2-Pad1)") (class "Default")
      (node (ref "CARD1") (pin "1") (pinfunction "DATA2_1") (pintype "bidirectional"))
    )
    (net (code "65") (name "unconnected-(DHT1-Pad3)") (class "Default")
      (node (ref "DHT1") (pin "3") (pinfunction "3_3") (pintype "passive+no_connect"))
    )
    (net (code "66") (name "unconnected-(J2-ID-Pad4)") (class "Default")
      (node (ref "J2") (pin "4") (pinfunction "ID_4") (pintype "passive+no_connect"))
    )
    (net (code "67") (name "unconnected-(Sensor1-NC-Pad7)") (class "Default")
      (node (ref "Sensor1") (pin "7") (pinfunction "NC_7") (pintype "passive+no_connect"))
    )
    (net (code "68") (name "unconnected-(Sensor1-NC-Pad8)") (class "Default")
      (node (ref "Sensor1") (pin "8") (pinfunction "NC_8") (pintype "passive+no_connect"))
    )
    (net (code "69") (name "unconnected-(U4-PA0-WKUP{slash}ADC12_IN0-Pad10)") (class "Default")
      (node (ref "U4") (pin "10") (pinfunction "PA0-WKUP/ADC12_IN0_10") (pintype "bidirectional"))
    )
    (net (code "70") (name "unconnected-(U4-PA1{slash}ADC12_IN1{slash}TIM2_CH2-Pad11)") (class "Default")
      (node (ref "U4") (pin "11") (pinfunction "PA1/ADC12_IN1/TIM2_CH2_11") (pintype "bidirectional"))
    )
    (net (code "71") (name "unconnected-(U4-PA4{slash}ADC12_IN4-Pad14)") (class "Default")
      (node (ref "U4") (pin "14") (pinfunction "PA4/ADC12_IN4_14") (pintype "bidirectional"))
    )
    (net (code "72") (name "unconnected-(U4-PA5{slash}SPI1_SCK-Pad15)") (class "Default")
      (node (ref "U4") (pin "15") (pinfunction "PA5/SPI1_SCK_15") (pintype "bidirectional"))
    )
  )
)
